# ftdi_eeprom.net
KiCad netlist of a schematic drawn in Altium Designer
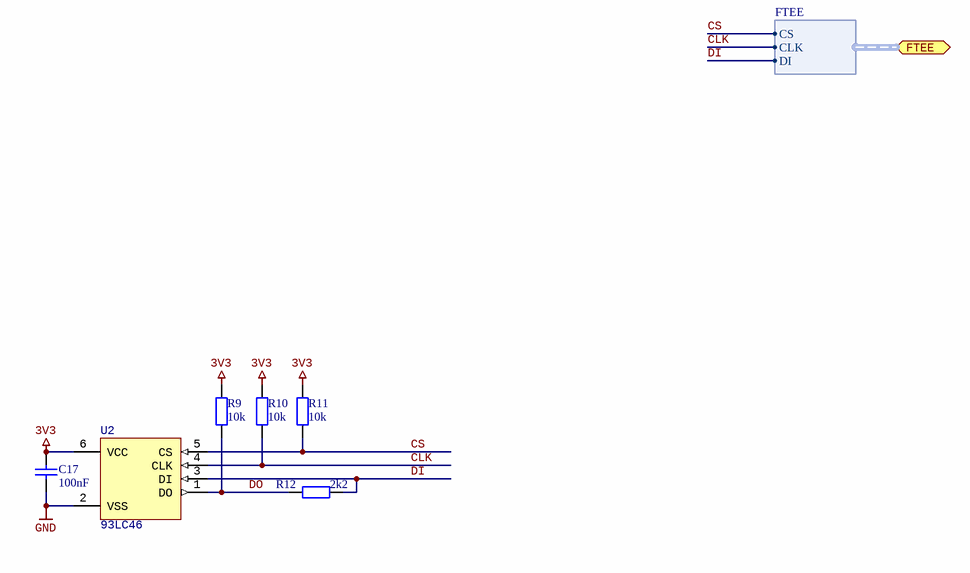
[diagram p0: ftdi_eeprom.SchDoc]

(export (version "E")
  (design (tool "Eeschema 10.0.6"))
  (components
    (comp (ref "C17")
      (value "100nF")
      (footprint "CAPC1608N")
      (description "Capacitor")
      (libsource (lib "Discrete") (part "Capacitor"))
    )
    (comp (ref "R9")
      (value "10k")
      (footprint "RESC1608N")
      (description "Resistor")
      (fields (field (name "TOLERANCE") "1%") (field (name "POWER") "0W"))
      (libsource (lib "") (part "Resistor_1"))
    )
    (comp (ref "R10")
      (value "10k")
      (footprint "RESC1608N")
      (description "Resistor")
      (fields (field (name "TOLERANCE") "1%") (field (name "POWER") "0W"))
      (libsource (lib "") (part "Resistor_1"))
    )
    (comp (ref "R11")
      (value "10k")
      (footprint "RESC1608N")
      (description "Resistor")
      (fields (field (name "TOLERANCE") "1%") (field (name "POWER") "0W"))
      (libsource (lib "") (part "Resistor_1"))
    )
    (comp (ref "R12")
      (value "2k2")
      (footprint "RESC1608N")
      (description "Resistor")
      (fields (field (name "TOLERANCE") "1%") (field (name "POWER") "0W"))
      (libsource (lib "Discrete") (part "Resistor"))
    )
    (comp (ref "U2")
      (value "93LC46")
      (footprint "SOT23-6")
      (description "1K Microwire Compatible Serial EEPROM")
      (libsource (lib "my_various_devices") (part "93LC46"))
    )
  )
  (nets
    (net (code "2") (name "/CLK") (class "Default")
      (node (ref "R10") (pin "2") (pinfunction "2_2") (pintype "passive"))
      (node (ref "U2") (pin "4") (pinfunction "CLK_4") (pintype "input"))
    )
    (net (code "3") (name "/CS") (class "Default")
      (node (ref "R11") (pin "2") (pinfunction "2_2") (pintype "passive"))
      (node (ref "U2") (pin "5") (pinfunction "CS_5") (pintype "input"))
    )
    (net (code "4") (name "/DI") (class "Default")
      (node (ref "R12") (pin "2") (pinfunction "2_2") (pintype "passive"))
      (node (ref "U2") (pin "3") (pinfunction "DI_3") (pintype "input"))
    )
    (net (code "5") (name "/DO") (class "Default")
      (node (ref "R12") (pin "1") (pinfunction "1_1") (pintype "passive"))
      (node (ref "R9") (pin "2") (pinfunction "2_2") (pintype "passive"))
      (node (ref "U2") (pin "1") (pinfunction "DO_1") (pintype "output"))
    )
    (net (code "7") (name "3V3") (class "Default")
      (node (ref "C17") (pin "2") (pinfunction "2_2") (pintype "passive"))
      (node (ref "R10") (pin "1") (pinfunction "1_1") (pintype "passive"))
      (node (ref "R11") (pin "1") (pinfunction "1_1") (pintype "passive"))
      (node (ref "R9") (pin "1") (pinfunction "1_1") (pintype "passive"))
      (node (ref "U2") (pin "6") (pinfunction "VCC_6") (pintype "power_in"))
    )
    (net (code "8") (name "GND") (class "Default")
      (node (ref "C17") (pin "1") (pinfunction "1_1") (pintype "passive"))
      (node (ref "U2") (pin "2") (pinfunction "VSS_2") (pintype "power_in"))
    )
  )
)
